# P-LED-0003-V1A_EAGLE_Schematic.net
KiCad netlist of a schematic drawn in EAGLE
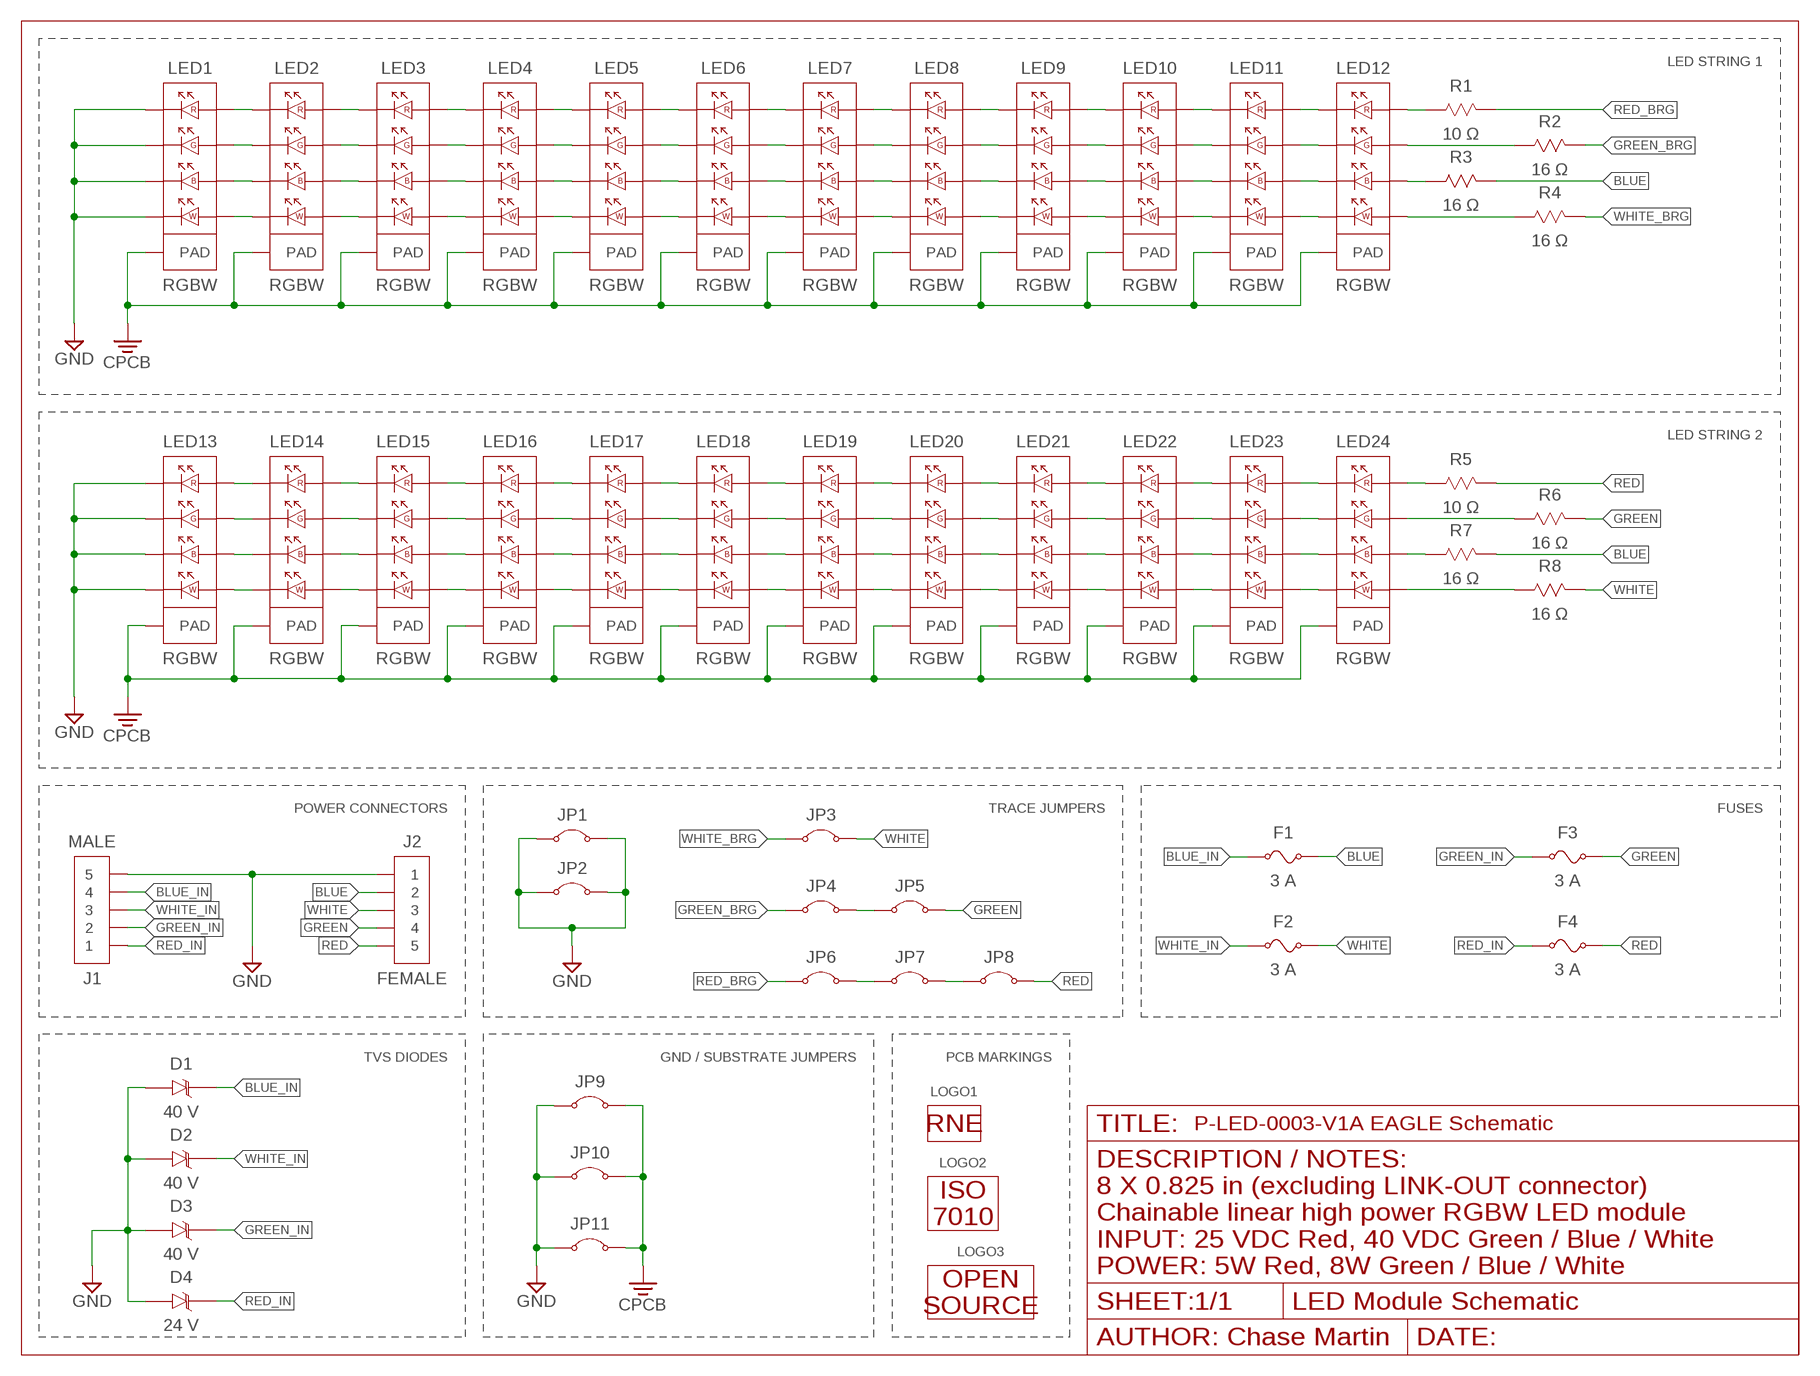
[diagram p0: schematic, sheet 1]

(export (version "E")
  (design (tool "Eeschema 10.0.6"))
  (components
    (comp (ref "D1")
      (value "40 V")
      (footprint "eagle-import:0603_POLARIZED")
      (libsource (lib "eagle-import") (part "UNIDIRECTIONAL_TVS_DIODESMD_0603"))
    )
    (comp (ref "D2")
      (value "40 V")
      (footprint "eagle-import:0603_POLARIZED")
      (libsource (lib "eagle-import") (part "UNIDIRECTIONAL_TVS_DIODESMD_0603"))
    )
    (comp (ref "D3")
      (value "40 V")
      (footprint "eagle-import:0603_POLARIZED")
      (libsource (lib "eagle-import") (part "UNIDIRECTIONAL_TVS_DIODESMD_0603"))
    )
    (comp (ref "D4")
      (value "24 V")
      (footprint "eagle-import:0603_POLARIZED")
      (libsource (lib "eagle-import") (part "UNIDIRECTIONAL_TVS_DIODESMD_0603"))
    )
    (comp (ref "F1")
      (value "3 A")
      (footprint "eagle-import:1206")
      (libsource (lib "eagle-import") (part "FUSESMD_1206"))
    )
    (comp (ref "F2")
      (value "3 A")
      (footprint "eagle-import:1206")
      (libsource (lib "eagle-import") (part "FUSESMD_1206"))
    )
    (comp (ref "F3")
      (value "3 A")
      (footprint "eagle-import:1206")
      (libsource (lib "eagle-import") (part "FUSESMD_1206"))
    )
    (comp (ref "F4")
      (value "3 A")
      (footprint "eagle-import:1206")
      (libsource (lib "eagle-import") (part "FUSESMD_1206"))
    )
    (comp (ref "J1")
      (value "MALE")
      (footprint "eagle-import:5-PIN_1-ROW_MALE_SMD_HORIZONTAL")
      (libsource (lib "eagle-import") (part "5-PIN_1-ROWMALE_SMD_HORIZONTAL"))
    )
    (comp (ref "J2")
      (value "FEMALE")
      (footprint "eagle-import:5-PIN_1-ROW_FEMALE_SMD_HORIZONTAL")
      (libsource (lib "eagle-import") (part "5-PIN_1-ROWFEMALE_SMD_HORIZONTAL"))
    )
    (comp (ref "JP1")
      (value "JUMPERSMD_1206")
      (footprint "eagle-import:1206")
      (libsource (lib "eagle-import") (part "JUMPERSMD_1206"))
    )
    (comp (ref "JP2")
      (value "JUMPERSMD_1206")
      (footprint "eagle-import:1206")
      (libsource (lib "eagle-import") (part "JUMPERSMD_1206"))
    )
    (comp (ref "JP3")
      (value "JUMPERSMD_1206")
      (footprint "eagle-import:1206")
      (libsource (lib "eagle-import") (part "JUMPERSMD_1206"))
    )
    (comp (ref "JP4")
      (value "JUMPERSMD_1206")
      (footprint "eagle-import:1206")
      (libsource (lib "eagle-import") (part "JUMPERSMD_1206"))
    )
    (comp (ref "JP5")
      (value "JUMPERSMD_1206")
      (footprint "eagle-import:1206")
      (libsource (lib "eagle-import") (part "JUMPERSMD_1206"))
    )
    (comp (ref "JP6")
      (value "JUMPERSMD_1206")
      (footprint "eagle-import:1206")
      (libsource (lib "eagle-import") (part "JUMPERSMD_1206"))
    )
    (comp (ref "JP7")
      (value "JUMPERSMD_1206")
      (footprint "eagle-import:1206")
      (libsource (lib "eagle-import") (part "JUMPERSMD_1206"))
    )
    (comp (ref "JP8")
      (value "JUMPERSMD_1206")
      (footprint "eagle-import:1206")
      (libsource (lib "eagle-import") (part "JUMPERSMD_1206"))
    )
    (comp (ref "JP9")
      (value "DCH_JUMPERSMD_0603")
      (footprint "eagle-import:0603")
      (libsource (lib "eagle-import") (part "DCH_JUMPERSMD_0603"))
    )
    (comp (ref "JP10")
      (value "DCH_JUMPERSMD_0603")
      (footprint "eagle-import:0603")
      (libsource (lib "eagle-import") (part "DCH_JUMPERSMD_0603"))
    )
    (comp (ref "JP11")
      (value "DCH_JUMPERSMD_0603")
      (footprint "eagle-import:0603")
      (libsource (lib "eagle-import") (part "DCH_JUMPERSMD_0603"))
    )
    (comp (ref "LED1")
      (value "RGBW")
      (footprint "eagle-import:IN-P55QSTGRGBW")
      (libsource (lib "eagle-import") (part "IN-P55QSTGRGBWPLCC8"))
    )
    (comp (ref "LED2")
      (value "RGBW")
      (footprint "eagle-import:IN-P55QSTGRGBW")
      (libsource (lib "eagle-import") (part "IN-P55QSTGRGBWPLCC8"))
    )
    (comp (ref "LED3")
      (value "RGBW")
      (footprint "eagle-import:IN-P55QSTGRGBW")
      (libsource (lib "eagle-import") (part "IN-P55QSTGRGBWPLCC8"))
    )
    (comp (ref "LED4")
      (value "RGBW")
      (footprint "eagle-import:IN-P55QSTGRGBW")
      (libsource (lib "eagle-import") (part "IN-P55QSTGRGBWPLCC8"))
    )
    (comp (ref "LED5")
      (value "RGBW")
      (footprint "eagle-import:IN-P55QSTGRGBW")
      (libsource (lib "eagle-import") (part "IN-P55QSTGRGBWPLCC8"))
    )
    (comp (ref "LED6")
      (value "RGBW")
      (footprint "eagle-import:IN-P55QSTGRGBW")
      (libsource (lib "eagle-import") (part "IN-P55QSTGRGBWPLCC8"))
    )
    (comp (ref "LED7")
      (value "RGBW")
      (footprint "eagle-import:IN-P55QSTGRGBW")
      (libsource (lib "eagle-import") (part "IN-P55QSTGRGBWPLCC8"))
    )
    (comp (ref "LED8")
      (value "RGBW")
      (footprint "eagle-import:IN-P55QSTGRGBW")
      (libsource (lib "eagle-import") (part "IN-P55QSTGRGBWPLCC8"))
    )
    (comp (ref "LED9")
      (value "RGBW")
      (footprint "eagle-import:IN-P55QSTGRGBW")
      (libsource (lib "eagle-import") (part "IN-P55QSTGRGBWPLCC8"))
    )
    (comp (ref "LED10")
      (value "RGBW")
      (footprint "eagle-import:IN-P55QSTGRGBW")
      (libsource (lib "eagle-import") (part "IN-P55QSTGRGBWPLCC8"))
    )
    (comp (ref "LED11")
      (value "RGBW")
      (footprint "eagle-import:IN-P55QSTGRGBW")
      (libsource (lib "eagle-import") (part "IN-P55QSTGRGBWPLCC8"))
    )
    (comp (ref "LED12")
      (value "RGBW")
      (footprint "eagle-import:IN-P55QSTGRGBW")
      (libsource (lib "eagle-import") (part "IN-P55QSTGRGBWPLCC8"))
    )
    (comp (ref "LED13")
      (value "RGBW")
      (footprint "eagle-import:IN-P55QSTGRGBW")
      (libsource (lib "eagle-import") (part "IN-P55QSTGRGBWPLCC8"))
    )
    (comp (ref "LED14")
      (value "RGBW")
      (footprint "eagle-import:IN-P55QSTGRGBW")
      (libsource (lib "eagle-import") (part "IN-P55QSTGRGBWPLCC8"))
    )
    (comp (ref "LED15")
      (value "RGBW")
      (footprint "eagle-import:IN-P55QSTGRGBW")
      (libsource (lib "eagle-import") (part "IN-P55QSTGRGBWPLCC8"))
    )
    (comp (ref "LED16")
      (value "RGBW")
      (footprint "eagle-import:IN-P55QSTGRGBW")
      (libsource (lib "eagle-import") (part "IN-P55QSTGRGBWPLCC8"))
    )
    (comp (ref "LED17")
      (value "RGBW")
      (footprint "eagle-import:IN-P55QSTGRGBW")
      (libsource (lib "eagle-import") (part "IN-P55QSTGRGBWPLCC8"))
    )
    (comp (ref "LED18")
      (value "RGBW")
      (footprint "eagle-import:IN-P55QSTGRGBW")
      (libsource (lib "eagle-import") (part "IN-P55QSTGRGBWPLCC8"))
    )
    (comp (ref "LED19")
      (value "RGBW")
      (footprint "eagle-import:IN-P55QSTGRGBW")
      (libsource (lib "eagle-import") (part "IN-P55QSTGRGBWPLCC8"))
    )
    (comp (ref "LED20")
      (value "RGBW")
      (footprint "eagle-import:IN-P55QSTGRGBW")
      (libsource (lib "eagle-import") (part "IN-P55QSTGRGBWPLCC8"))
    )
    (comp (ref "LED21")
      (value "RGBW")
      (footprint "eagle-import:IN-P55QSTGRGBW")
      (libsource (lib "eagle-import") (part "IN-P55QSTGRGBWPLCC8"))
    )
    (comp (ref "LED22")
      (value "RGBW")
      (footprint "eagle-import:IN-P55QSTGRGBW")
      (libsource (lib "eagle-import") (part "IN-P55QSTGRGBWPLCC8"))
    )
    (comp (ref "LED23")
      (value "RGBW")
      (footprint "eagle-import:IN-P55QSTGRGBW")
      (libsource (lib "eagle-import") (part "IN-P55QSTGRGBWPLCC8"))
    )
    (comp (ref "LED24")
      (value "RGBW")
      (footprint "eagle-import:IN-P55QSTGRGBW")
      (libsource (lib "eagle-import") (part "IN-P55QSTGRGBWPLCC8"))
    )
    (comp (ref "LOGO1")
      (value "PROFILE_LOGO_RNE0.375\"")
      (footprint "eagle-import:RNE_PROFILE-LOGO_375")
      (libsource (lib "eagle-import") (part "PROFILE_LOGO_RNE0.375{dblquote}"))
    )
    (comp (ref "LOGO2")
      (value "HOT_SURFACE_ISO0.375\"_LABEL")
      (footprint "eagle-import:ISO_HOT-SURFACE_375_LABEL")
      (libsource (lib "eagle-import") (part "HOT_SURFACE_ISO0.375{dblquote}_LABEL"))
    )
    (comp (ref "LOGO3")
      (value "OPEN_SOURCE_OSHWA0.375\"_LABEL")
      (footprint "eagle-import:OSHWA_OPEN-SOURCE_375_LABEL")
      (libsource (lib "eagle-import") (part "OPEN_SOURCE_OSHWA0.375{dblquote}_LABEL"))
    )
    (comp (ref "R1")
      (value "10 Ω")
      (footprint "eagle-import:0603")
      (libsource (lib "eagle-import") (part "RESISTORSMD_0603"))
    )
    (comp (ref "R2")
      (value "16 Ω")
      (footprint "eagle-import:0603")
      (libsource (lib "eagle-import") (part "RESISTORSMD_0603"))
    )
    (comp (ref "R3")
      (value "16 Ω")
      (footprint "eagle-import:0603")
      (libsource (lib "eagle-import") (part "RESISTORSMD_0603"))
    )
    (comp (ref "R4")
      (value "16 Ω")
      (footprint "eagle-import:0603")
      (libsource (lib "eagle-import") (part "RESISTORSMD_0603"))
    )
    (comp (ref "R5")
      (value "10 Ω")
      (footprint "eagle-import:0603")
      (libsource (lib "eagle-import") (part "RESISTORSMD_0603"))
    )
    (comp (ref "R6")
      (value "16 Ω")
      (footprint "eagle-import:0603")
      (libsource (lib "eagle-import") (part "RESISTORSMD_0603"))
    )
    (comp (ref "R7")
      (value "16 Ω")
      (footprint "eagle-import:0603")
      (libsource (lib "eagle-import") (part "RESISTORSMD_0603"))
    )
    (comp (ref "R8")
      (value "16 Ω")
      (footprint "eagle-import:0603")
      (libsource (lib "eagle-import") (part "RESISTORSMD_0603"))
    )
  )
  (nets
    (net (code "1") (name "BLUE") (class "Default")
      (node (ref "F1") (pin "2") (pinfunction "2_2") (pintype "passive"))
      (node (ref "J2") (pin "2") (pinfunction "2_2") (pintype "passive"))
      (node (ref "R3") (pin "2") (pinfunction "2_2") (pintype "passive"))
      (node (ref "R7") (pin "2") (pinfunction "2_2") (pintype "passive"))
    )
    (net (code "2") (name "BLUE_IN") (class "Default")
      (node (ref "D1") (pin "K") (pinfunction "K_K") (pintype "passive"))
      (node (ref "F1") (pin "1") (pinfunction "1_1") (pintype "passive"))
      (node (ref "J1") (pin "4") (pinfunction "4_4") (pintype "passive"))
    )
    (net (code "3") (name "CPCB") (class "Default")
      (node (ref "JP10") (pin "2") (pinfunction "2_2") (pintype "passive"))
      (node (ref "JP11") (pin "2") (pinfunction "2_2") (pintype "passive"))
      (node (ref "JP9") (pin "2") (pinfunction "2_2") (pintype "passive"))
      (node (ref "LED1") (pin "PAD") (pinfunction "PAD_PAD") (pintype "passive"))
      (node (ref "LED10") (pin "PAD") (pinfunction "PAD_PAD") (pintype "passive"))
      (node (ref "LED11") (pin "PAD") (pinfunction "PAD_PAD") (pintype "passive"))
      (node (ref "LED12") (pin "PAD") (pinfunction "PAD_PAD") (pintype "passive"))
      (node (ref "LED13") (pin "PAD") (pinfunction "PAD_PAD") (pintype "passive"))
      (node (ref "LED14") (pin "PAD") (pinfunction "PAD_PAD") (pintype "passive"))
      (node (ref "LED15") (pin "PAD") (pinfunction "PAD_PAD") (pintype "passive"))
      (node (ref "LED16") (pin "PAD") (pinfunction "PAD_PAD") (pintype "passive"))
      (node (ref "LED17") (pin "PAD") (pinfunction "PAD_PAD") (pintype "passive"))
      (node (ref "LED18") (pin "PAD") (pinfunction "PAD_PAD") (pintype "passive"))
      (node (ref "LED19") (pin "PAD") (pinfunction "PAD_PAD") (pintype "passive"))
      (node (ref "LED2") (pin "PAD") (pinfunction "PAD_PAD") (pintype "passive"))
      (node (ref "LED20") (pin "PAD") (pinfunction "PAD_PAD") (pintype "passive"))
      (node (ref "LED21") (pin "PAD") (pinfunction "PAD_PAD") (pintype "passive"))
      (node (ref "LED22") (pin "PAD") (pinfunction "PAD_PAD") (pintype "passive"))
      (node (ref "LED23") (pin "PAD") (pinfunction "PAD_PAD") (pintype "passive"))
      (node (ref "LED24") (pin "PAD") (pinfunction "PAD_PAD") (pintype "passive"))
      (node (ref "LED3") (pin "PAD") (pinfunction "PAD_PAD") (pintype "passive"))
      (node (ref "LED4") (pin "PAD") (pinfunction "PAD_PAD") (pintype "passive"))
      (node (ref "LED5") (pin "PAD") (pinfunction "PAD_PAD") (pintype "passive"))
      (node (ref "LED6") (pin "PAD") (pinfunction "PAD_PAD") (pintype "passive"))
      (node (ref "LED7") (pin "PAD") (pinfunction "PAD_PAD") (pintype "passive"))
      (node (ref "LED8") (pin "PAD") (pinfunction "PAD_PAD") (pintype "passive"))
      (node (ref "LED9") (pin "PAD") (pinfunction "PAD_PAD") (pintype "passive"))
    )
    (net (code "4") (name "GND") (class "Default")
      (node (ref "D1") (pin "A") (pinfunction "A_A") (pintype "passive"))
      (node (ref "D2") (pin "A") (pinfunction "A_A") (pintype "passive"))
      (node (ref "D3") (pin "A") (pinfunction "A_A") (pintype "passive"))
      (node (ref "D4") (pin "A") (pinfunction "A_A") (pintype "passive"))
      (node (ref "J1") (pin "5") (pinfunction "5_5") (pintype "passive"))
      (node (ref "J2") (pin "1") (pinfunction "1_1") (pintype "passive"))
      (node (ref "JP1") (pin "1") (pinfunction "1_1") (pintype "passive"))
      (node (ref "JP1") (pin "2") (pinfunction "2_2") (pintype "passive"))
      (node (ref "JP10") (pin "1") (pinfunction "1_1") (pintype "passive"))
      (node (ref "JP11") (pin "1") (pinfunction "1_1") (pintype "passive"))
      (node (ref "JP2") (pin "1") (pinfunction "1_1") (pintype "passive"))
      (node (ref "JP2") (pin "2") (pinfunction "2_2") (pintype "passive"))
      (node (ref "JP9") (pin "1") (pinfunction "1_1") (pintype "passive"))
      (node (ref "LED1") (pin "BLUE_N") (pinfunction "BLUE_N_BLUE_N") (pintype "output"))
      (node (ref "LED1") (pin "GREEN_N") (pinfunction "GREEN_N_GREEN_N") (pintype "output"))
      (node (ref "LED1") (pin "RED_N") (pinfunction "RED_N_RED_N") (pintype "output"))
      (node (ref "LED1") (pin "WHITE_N") (pinfunction "WHITE_N_WHITE_N") (pintype "output"))
      (node (ref "LED13") (pin "BLUE_N") (pinfunction "BLUE_N_BLUE_N") (pintype "output"))
      (node (ref "LED13") (pin "GREEN_N") (pinfunction "GREEN_N_GREEN_N") (pintype "output"))
      (node (ref "LED13") (pin "RED_N") (pinfunction "RED_N_RED_N") (pintype "output"))
      (node (ref "LED13") (pin "WHITE_N") (pinfunction "WHITE_N_WHITE_N") (pintype "output"))
    )
    (net (code "5") (name "GREEN") (class "Default")
      (node (ref "F3") (pin "2") (pinfunction "2_2") (pintype "passive"))
      (node (ref "J2") (pin "4") (pinfunction "4_4") (pintype "passive"))
      (node (ref "JP5") (pin "2") (pinfunction "2_2") (pintype "passive"))
      (node (ref "R6") (pin "2") (pinfunction "2_2") (pintype "passive"))
    )
    (net (code "6") (name "GREEN_BRG") (class "Default")
      (node (ref "JP4") (pin "1") (pinfunction "1_1") (pintype "passive"))
      (node (ref "R2") (pin "2") (pinfunction "2_2") (pintype "passive"))
    )
    (net (code "7") (name "GREEN_IN") (class "Default")
      (node (ref "D3") (pin "K") (pinfunction "K_K") (pintype "passive"))
      (node (ref "F3") (pin "1") (pinfunction "1_1") (pintype "passive"))
      (node (ref "J1") (pin "2") (pinfunction "2_2") (pintype "passive"))
    )
    (net (code "8") (name "Net-(JP4-Pad2)") (class "Default")
      (node (ref "JP4") (pin "2") (pinfunction "2_2") (pintype "passive"))
      (node (ref "JP5") (pin "1") (pinfunction "1_1") (pintype "passive"))
    )
    (net (code "9") (name "Net-(JP6-Pad2)") (class "Default")
      (node (ref "JP6") (pin "2") (pinfunction "2_2") (pintype "passive"))
      (node (ref "JP7") (pin "1") (pinfunction "1_1") (pintype "passive"))
    )
    (net (code "10") (name "Net-(JP7-Pad2)") (class "Default")
      (node (ref "JP7") (pin "2") (pinfunction "2_2") (pintype "passive"))
      (node (ref "JP8") (pin "1") (pinfunction "1_1") (pintype "passive"))
    )
    (net (code "11") (name "Net-(LED1-PadBLUE_P)") (class "Default")
      (node (ref "LED1") (pin "BLUE_P") (pinfunction "BLUE_P_BLUE_P") (pintype "input"))
      (node (ref "LED2") (pin "BLUE_N") (pinfunction "BLUE_N_BLUE_N") (pintype "output"))
    )
    (net (code "12") (name "Net-(LED1-PadGREEN_P)") (class "Default")
      (node (ref "LED1") (pin "GREEN_P") (pinfunction "GREEN_P_GREEN_P") (pintype "input"))
      (node (ref "LED2") (pin "GREEN_N") (pinfunction "GREEN_N_GREEN_N") (pintype "output"))
    )
    (net (code "13") (name "Net-(LED1-PadRED_P)") (class "Default")
      (node (ref "LED1") (pin "RED_P") (pinfunction "RED_P_RED_P") (pintype "input"))
      (node (ref "LED2") (pin "RED_N") (pinfunction "RED_N_RED_N") (pintype "output"))
    )
    (net (code "14") (name "Net-(LED1-PadWHITE_P)") (class "Default")
      (node (ref "LED1") (pin "WHITE_P") (pinfunction "WHITE_P_WHITE_P") (pintype "input"))
      (node (ref "LED2") (pin "WHITE_N") (pinfunction "WHITE_N_WHITE_N") (pintype "output"))
    )
    (net (code "15") (name "Net-(LED2-PadBLUE_P)") (class "Default")
      (node (ref "LED2") (pin "BLUE_P") (pinfunction "BLUE_P_BLUE_P") (pintype "input"))
      (node (ref "LED3") (pin "BLUE_N") (pinfunction "BLUE_N_BLUE_N") (pintype "output"))
    )
    (net (code "16") (name "Net-(LED2-PadGREEN_P)") (class "Default")
      (node (ref "LED2") (pin "GREEN_P") (pinfunction "GREEN_P_GREEN_P") (pintype "input"))
      (node (ref "LED3") (pin "GREEN_N") (pinfunction "GREEN_N_GREEN_N") (pintype "output"))
    )
    (net (code "17") (name "Net-(LED2-PadRED_P)") (class "Default")
      (node (ref "LED2") (pin "RED_P") (pinfunction "RED_P_RED_P") (pintype "input"))
      (node (ref "LED3") (pin "RED_N") (pinfunction "RED_N_RED_N") (pintype "output"))
    )
    (net (code "18") (name "Net-(LED2-PadWHITE_P)") (class "Default")
      (node (ref "LED2") (pin "WHITE_P") (pinfunction "WHITE_P_WHITE_P") (pintype "input"))
      (node (ref "LED3") (pin "WHITE_N") (pinfunction "WHITE_N_WHITE_N") (pintype "output"))
    )
    (net (code "19") (name "Net-(LED3-PadBLUE_P)") (class "Default")
      (node (ref "LED3") (pin "BLUE_P") (pinfunction "BLUE_P_BLUE_P") (pintype "input"))
      (node (ref "LED4") (pin "BLUE_N") (pinfunction "BLUE_N_BLUE_N") (pintype "output"))
    )
    (net (code "20") (name "Net-(LED3-PadGREEN_P)") (class "Default")
      (node (ref "LED3") (pin "GREEN_P") (pinfunction "GREEN_P_GREEN_P") (pintype "input"))
      (node (ref "LED4") (pin "GREEN_N") (pinfunction "GREEN_N_GREEN_N") (pintype "output"))
    )
    (net (code "21") (name "Net-(LED3-PadRED_P)") (class "Default")
      (node (ref "LED3") (pin "RED_P") (pinfunction "RED_P_RED_P") (pintype "input"))
      (node (ref "LED4") (pin "RED_N") (pinfunction "RED_N_RED_N") (pintype "output"))
    )
    (net (code "22") (name "Net-(LED3-PadWHITE_P)") (class "Default")
      (node (ref "LED3") (pin "WHITE_P") (pinfunction "WHITE_P_WHITE_P") (pintype "input"))
      (node (ref "LED4") (pin "WHITE_N") (pinfunction "WHITE_N_WHITE_N") (pintype "output"))
    )
    (net (code "23") (name "Net-(LED4-PadBLUE_P)") (class "Default")
      (node (ref "LED4") (pin "BLUE_P") (pinfunction "BLUE_P_BLUE_P") (pintype "input"))
      (node (ref "LED5") (pin "BLUE_N") (pinfunction "BLUE_N_BLUE_N") (pintype "output"))
    )
    (net (code "24") (name "Net-(LED4-PadGREEN_P)") (class "Default")
      (node (ref "LED4") (pin "GREEN_P") (pinfunction "GREEN_P_GREEN_P") (pintype "input"))
      (node (ref "LED5") (pin "GREEN_N") (pinfunction "GREEN_N_GREEN_N") (pintype "output"))
    )
    (net (code "25") (name "Net-(LED4-PadRED_P)") (class "Default")
      (node (ref "LED4") (pin "RED_P") (pinfunction "RED_P_RED_P") (pintype "input"))
      (node (ref "LED5") (pin "RED_N") (pinfunction "RED_N_RED_N") (pintype "output"))
    )
    (net (code "26") (name "Net-(LED4-PadWHITE_P)") (class "Default")
      (node (ref "LED4") (pin "WHITE_P") (pinfunction "WHITE_P_WHITE_P") (pintype "input"))
      (node (ref "LED5") (pin "WHITE_N") (pinfunction "WHITE_N_WHITE_N") (pintype "output"))
    )
    (net (code "27") (name "Net-(LED5-PadBLUE_P)") (class "Default")
      (node (ref "LED5") (pin "BLUE_P") (pinfunction "BLUE_P_BLUE_P") (pintype "input"))
      (node (ref "LED6") (pin "BLUE_N") (pinfunction "BLUE_N_BLUE_N") (pintype "output"))
    )
    (net (code "28") (name "Net-(LED5-PadGREEN_P)") (class "Default")
      (node (ref "LED5") (pin "GREEN_P") (pinfunction "GREEN_P_GREEN_P") (pintype "input"))
      (node (ref "LED6") (pin "GREEN_N") (pinfunction "GREEN_N_GREEN_N") (pintype "output"))
    )
    (net (code "29") (name "Net-(LED5-PadRED_P)") (class "Default")
      (node (ref "LED5") (pin "RED_P") (pinfunction "RED_P_RED_P") (pintype "input"))
      (node (ref "LED6") (pin "RED_N") (pinfunction "RED_N_RED_N") (pintype "output"))
    )
    (net (code "30") (name "Net-(LED5-PadWHITE_P)") (class "Default")
      (node (ref "LED5") (pin "WHITE_P") (pinfunction "WHITE_P_WHITE_P") (pintype "input"))
      (node (ref "LED6") (pin "WHITE_N") (pinfunction "WHITE_N_WHITE_N") (pintype "output"))
    )
    (net (code "31") (name "Net-(LED6-PadBLUE_P)") (class "Default")
      (node (ref "LED6") (pin "BLUE_P") (pinfunction "BLUE_P_BLUE_P") (pintype "input"))
      (node (ref "LED7") (pin "BLUE_N") (pinfunction "BLUE_N_BLUE_N") (pintype "output"))
    )
    (net (code "32") (name "Net-(LED6-PadGREEN_P)") (class "Default")
      (node (ref "LED6") (pin "GREEN_P") (pinfunction "GREEN_P_GREEN_P") (pintype "input"))
      (node (ref "LED7") (pin "GREEN_N") (pinfunction "GREEN_N_GREEN_N") (pintype "output"))
    )
    (net (code "33") (name "Net-(LED6-PadRED_P)") (class "Default")
      (node (ref "LED6") (pin "RED_P") (pinfunction "RED_P_RED_P") (pintype "input"))
      (node (ref "LED7") (pin "RED_N") (pinfunction "RED_N_RED_N") (pintype "output"))
    )
    (net (code "34") (name "Net-(LED6-PadWHITE_P)") (class "Default")
      (node (ref "LED6") (pin "WHITE_P") (pinfunction "WHITE_P_WHITE_P") (pintype "input"))
      (node (ref "LED7") (pin "WHITE_N") (pinfunction "WHITE_N_WHITE_N") (pintype "output"))
    )
    (net (code "35") (name "Net-(LED7-PadBLUE_P)") (class "Default")
      (node (ref "LED7") (pin "BLUE_P") (pinfunction "BLUE_P_BLUE_P") (pintype "input"))
      (node (ref "LED8") (pin "BLUE_N") (pinfunction "BLUE_N_BLUE_N") (pintype "output"))
    )
    (net (code "36") (name "Net-(LED7-PadGREEN_P)") (class "Default")
      (node (ref "LED7") (pin "GREEN_P") (pinfunction "GREEN_P_GREEN_P") (pintype "input"))
      (node (ref "LED8") (pin "GREEN_N") (pinfunction "GREEN_N_GREEN_N") (pintype "output"))
    )
    (net (code "37") (name "Net-(LED7-PadRED_P)") (class "Default")
      (node (ref "LED7") (pin "RED_P") (pinfunction "RED_P_RED_P") (pintype "input"))
      (node (ref "LED8") (pin "RED_N") (pinfunction "RED_N_RED_N") (pintype "output"))
    )
    (net (code "38") (name "Net-(LED7-PadWHITE_P)") (class "Default")
      (node (ref "LED7") (pin "WHITE_P") (pinfunction "WHITE_P_WHITE_P") (pintype "input"))
      (node (ref "LED8") (pin "WHITE_N") (pinfunction "WHITE_N_WHITE_N") (pintype "output"))
    )
    (net (code "39") (name "Net-(LED8-PadBLUE_P)") (class "Default")
      (node (ref "LED8") (pin "BLUE_P") (pinfunction "BLUE_P_BLUE_P") (pintype "input"))
      (node (ref "LED9") (pin "BLUE_N") (pinfunction "BLUE_N_BLUE_N") (pintype "output"))
    )
    (net (code "40") (name "Net-(LED8-PadGREEN_P)") (class "Default")
      (node (ref "LED8") (pin "GREEN_P") (pinfunction "GREEN_P_GREEN_P") (pintype "input"))
      (node (ref "LED9") (pin "GREEN_N") (pinfunction "GREEN_N_GREEN_N") (pintype "output"))
    )
    (net (code "41") (name "Net-(LED8-PadRED_P)") (class "Default")
      (node (ref "LED8") (pin "RED_P") (pinfunction "RED_P_RED_P") (pintype "input"))
      (node (ref "LED9") (pin "RED_N") (pinfunction "RED_N_RED_N") (pintype "output"))
    )
    (net (code "42") (name "Net-(LED8-PadWHITE_P)") (class "Default")
      (node (ref "LED8") (pin "WHITE_P") (pinfunction "WHITE_P_WHITE_P") (pintype "input"))
      (node (ref "LED9") (pin "WHITE_N") (pinfunction "WHITE_N_WHITE_N") (pintype "output"))
    )
    (net (code "43") (name "Net-(LED10-PadBLUE_N)") (class "Default")
      (node (ref "LED10") (pin "BLUE_N") (pinfunction "BLUE_N_BLUE_N") (pintype "output"))
      (node (ref "LED9") (pin "BLUE_P") (pinfunction "BLUE_P_BLUE_P") (pintype "input"))
    )
    (net (code "44") (name "Net-(LED10-PadBLUE_P)") (class "Default")
      (node (ref "LED10") (pin "BLUE_P") (pinfunction "BLUE_P_BLUE_P") (pintype "input"))
      (node (ref "LED11") (pin "BLUE_N") (pinfunction "BLUE_N_BLUE_N") (pintype "output"))
    )
    (net (code "45") (name "Net-(LED10-PadGREEN_N)") (class "Default")
      (node (ref "LED10") (pin "GREEN_N") (pinfunction "GREEN_N_GREEN_N") (pintype "output"))
      (node (ref "LED9") (pin "GREEN_P") (pinfunction "GREEN_P_GREEN_P") (pintype "input"))
    )
    (net (code "46") (name "Net-(LED10-PadGREEN_P)") (class "Default")
      (node (ref "LED10") (pin "GREEN_P") (pinfunction "GREEN_P_GREEN_P") (pintype "input"))
      (node (ref "LED11") (pin "GREEN_N") (pinfunction "GREEN_N_GREEN_N") (pintype "output"))
    )
    (net (code "47") (name "Net-(LED10-PadRED_N)") (class "Default")
      (node (ref "LED10") (pin "RED_N") (pinfunction "RED_N_RED_N") (pintype "output"))
      (node (ref "LED9") (pin "RED_P") (pinfunction "RED_P_RED_P") (pintype "input"))
    )
    (net (code "48") (name "Net-(LED10-PadRED_P)") (class "Default")
      (node (ref "LED10") (pin "RED_P") (pinfunction "RED_P_RED_P") (pintype "input"))
      (node (ref "LED11") (pin "RED_N") (pinfunction "RED_N_RED_N") (pintype "output"))
    )
    (net (code "49") (name "Net-(LED10-PadWHITE_N)") (class "Default")
      (node (ref "LED10") (pin "WHITE_N") (pinfunction "WHITE_N_WHITE_N") (pintype "output"))
      (node (ref "LED9") (pin "WHITE_P") (pinfunction "WHITE_P_WHITE_P") (pintype "input"))
    )
    (net (code "50") (name "Net-(LED10-PadWHITE_P)") (class "Default")
      (node (ref "LED10") (pin "WHITE_P") (pinfunction "WHITE_P_WHITE_P") (pintype "input"))
      (node (ref "LED11") (pin "WHITE_N") (pinfunction "WHITE_N_WHITE_N") (pintype "output"))
    )
    (net (code "51") (name "Net-(LED11-PadBLUE_P)") (class "Default")
      (node (ref "LED11") (pin "BLUE_P") (pinfunction "BLUE_P_BLUE_P") (pintype "input"))
      (node (ref "LED12") (pin "BLUE_N") (pinfunction "BLUE_N_BLUE_N") (pintype "output"))
    )
    (net (code "52") (name "Net-(LED11-PadGREEN_P)") (class "Default")
      (node (ref "LED11") (pin "GREEN_P") (pinfunction "GREEN_P_GREEN_P") (pintype "input"))
      (node (ref "LED12") (pin "GREEN_N") (pinfunction "GREEN_N_GREEN_N") (pintype "output"))
    )
    (net (code "53") (name "Net-(LED11-PadRED_P)") (class "Default")
      (node (ref "LED11") (pin "RED_P") (pinfunction "RED_P_RED_P") (pintype "input"))
      (node (ref "LED12") (pin "RED_N") (pinfunction "RED_N_RED_N") (pintype "output"))
    )
    (net (code "54") (name "Net-(LED11-PadWHITE_P)") (class "Default")
      (node (ref "LED11") (pin "WHITE_P") (pinfunction "WHITE_P_WHITE_P") (pintype "input"))
      (node (ref "LED12") (pin "WHITE_N") (pinfunction "WHITE_N_WHITE_N") (pintype "output"))
    )
    (net (code "55") (name "Net-(LED12-PadBLUE_P)") (class "Default")
      (node (ref "LED12") (pin "BLUE_P") (pinfunction "BLUE_P_BLUE_P") (pintype "input"))
      (node (ref "R3") (pin "1") (pinfunction "1_1") (pintype "passive"))
    )
    (net (code "56") (name "Net-(LED12-PadGREEN_P)") (class "Default")
      (node (ref "LED12") (pin "GREEN_P") (pinfunction "GREEN_P_GREEN_P") (pintype "input"))
      (node (ref "R2") (pin "1") (pinfunction "1_1") (pintype "passive"))
    )
    (net (code "57") (name "Net-(LED12-PadRED_P)") (class "Default")
      (node (ref "LED12") (pin "RED_P") (pinfunction "RED_P_RED_P") (pintype "input"))
      (node (ref "R1") (pin "1") (pinfunction "1_1") (pintype "passive"))
    )
    (net (code "58") (name "Net-(LED12-PadWHITE_P)") (class "Default")
      (node (ref "LED12") (pin "WHITE_P") (pinfunction "WHITE_P_WHITE_P") (pintype "input"))
      (node (ref "R4") (pin "1") (pinfunction "1_1") (pintype "passive"))
    )
    (net (code "59") (name "Net-(LED13-PadBLUE_P)") (class "Default")
      (node (ref "LED13") (pin "BLUE_P") (pinfunction "BLUE_P_BLUE_P") (pintype "input"))
      (node (ref "LED14") (pin "BLUE_N") (pinfunction "BLUE_N_BLUE_N") (pintype "output"))
    )
    (net (code "60") (name "Net-(LED13-PadGREEN_P)") (class "Default")
      (node (ref "LED13") (pin "GREEN_P") (pinfunction "GREEN_P_GREEN_P") (pintype "input"))
      (node (ref "LED14") (pin "GREEN_N") (pinfunction "GREEN_N_GREEN_N") (pintype "output"))
    )
    (net (code "61") (name "Net-(LED13-PadRED_P)") (class "Default")
      (node (ref "LED13") (pin "RED_P") (pinfunction "RED_P_RED_P") (pintype "input"))
      (node (ref "LED14") (pin "RED_N") (pinfunction "RED_N_RED_N") (pintype "output"))
    )
    (net (code "62") (name "Net-(LED13-PadWHITE_P)") (class "Default")
      (node (ref "LED13") (pin "WHITE_P") (pinfunction "WHITE_P_WHITE_P") (pintype "input"))
      (node (ref "LED14") (pin "WHITE_N") (pinfunction "WHITE_N_WHITE_N") (pintype "output"))
    )
    (net (code "63") (name "Net-(LED14-PadBLUE_P)") (class "Default")
      (node (ref "LED14") (pin "BLUE_P") (pinfunction "BLUE_P_BLUE_P") (pintype "input"))
      (node (ref "LED15") (pin "BLUE_N") (pinfunction "BLUE_N_BLUE_N") (pintype "output"))
    )
    (net (code "64") (name "Net-(LED14-PadGREEN_P)") (class "Default")
      (node (ref "LED14") (pin "GREEN_P") (pinfunction "GREEN_P_GREEN_P") (pintype "input"))
      (node (ref "LED15") (pin "GREEN_N") (pinfunction "GREEN_N_GREEN_N") (pintype "output"))
    )
    (net (code "65") (name "Net-(LED14-PadRED_P)") (class "Default")
      (node (ref "LED14") (pin "RED_P") (pinfunction "RED_P_RED_P") (pintype "input"))
      (node (ref "LED15") (pin "RED_N") (pinfunction "RED_N_RED_N") (pintype "output"))
    )
    (net (code "66") (name "Net-(LED14-PadWHITE_P)") (class "Default")
      (node (ref "LED14") (pin "WHITE_P") (pinfunction "WHITE_P_WHITE_P") (pintype "input"))
      (node (ref "LED15") (pin "WHITE_N") (pinfunction "WHITE_N_WHITE_N") (pintype "output"))
    )
    (net (code "67") (name "Net-(LED15-PadBLUE_P)") (class "Default")
      (node (ref "LED15") (pin "BLUE_P") (pinfunction "BLUE_P_BLUE_P") (pintype "input"))
      (node (ref "LED16") (pin "BLUE_N") (pinfunction "BLUE_N_BLUE_N") (pintype "output"))
    )
    (net (code "68") (name "Net-(LED15-PadGREEN_P)") (class "Default")
      (node (ref "LED15") (pin "GREEN_P") (pinfunction "GREEN_P_GREEN_P") (pintype "input"))
      (node (ref "LED16") (pin "GREEN_N") (pinfunction "GREEN_N_GREEN_N") (pintype "output"))
    )
    (net (code "69") (name "Net-(LED15-PadRED_P)") (class "Default")
      (node (ref "LED15") (pin "RED_P") (pinfunction "RED_P_RED_P") (pintype "input"))
      (node (ref "LED16") (pin "RED_N") (pinfunction "RED_N_RED_N") (pintype "output"))
    )
    (net (code "70") (name "Net-(LED15-PadWHITE_P)") (class "Default")
      (node (ref "LED15") (pin "WHITE_P") (pinfunction "WHITE_P_WHITE_P") (pintype "input"))
      (node (ref "LED16") (pin "WHITE_N") (pinfunction "WHITE_N_WHITE_N") (pintype "output"))
    )
    (net (code "71") (name "Net-(LED16-PadBLUE_P)") (class "Default")
      (node (ref "LED16") (pin "BLUE_P") (pinfunction "BLUE_P_BLUE_P") (pintype "input"))
      (node (ref "LED17") (pin "BLUE_N") (pinfunction "BLUE_N_BLUE_N") (pintype "output"))
    )
    (net (code "72") (name "Net-(LED16-PadGREEN_P)") (class "Default")
      (node (ref "LED16") (pin "GREEN_P") (pinfunction "GREEN_P_GREEN_P") (pintype "input"))
      (node (ref "LED17") (pin "GREEN_N") (pinfunction "GREEN_N_GREEN_N") (pintype "output"))
    )
    (net (code "73") (name "Net-(LED16-PadRED_P)") (class "Default")
      (node (ref "LED16") (pin "RED_P") (pinfunction "RED_P_RED_P") (pintype "input"))
      (node (ref "LED17") (pin "RED_N") (pinfunction "RED_N_RED_N") (pintype "output"))
    )
    (net (code "74") (name "Net-(LED16-PadWHITE_P)") (class "Default")
      (node (ref "LED16") (pin "WHITE_P") (pinfunction "WHITE_P_WHITE_P") (pintype "input"))
      (node (ref "LED17") (pin "WHITE_N") (pinfunction "WHITE_N_WHITE_N") (pintype "output"))
    )
    (net (code "75") (name "Net-(LED17-PadBLUE_P)") (class "Default")
      (node (ref "LED17") (pin "BLUE_P") (pinfunction "BLUE_P_BLUE_P") (pintype "input"))
      (node (ref "LED18") (pin "BLUE_N") (pinfunction "BLUE_N_BLUE_N") (pintype "output"))
    )
    (net (code "76") (name "Net-(LED17-PadGREEN_P)") (class "Default")
      (node (ref "LED17") (pin "GREEN_P") (pinfunction "GREEN_P_GREEN_P") (pintype "input"))
      (node (ref "LED18") (pin "GREEN_N") (pinfunction "GREEN_N_GREEN_N") (pintype "output"))
    )
    (net (code "77") (name "Net-(LED17-PadRED_P)") (class "Default")
      (node (ref "LED17") (pin "RED_P") (pinfunction "RED_P_RED_P") (pintype "input"))
      (node (ref "LED18") (pin "RED_N") (pinfunction "RED_N_RED_N") (pintype "output"))
    )
    (net (code "78") (name "Net-(LED17-PadWHITE_P)") (class "Default")
      (node (ref "LED17") (pin "WHITE_P") (pinfunction "WHITE_P_WHITE_P") (pintype "input"))
      (node (ref "LED18") (pin "WHITE_N") (pinfunction "WHITE_N_WHITE_N") (pintype "output"))
    )
    (net (code "79") (name "Net-(LED18-PadBLUE_P)") (class "Default")
      (node (ref "LED18") (pin "BLUE_P") (pinfunction "BLUE_P_BLUE_P") (pintype "input"))
      (node (ref "LED19") (pin "BLUE_N") (pinfunction "BLUE_N_BLUE_N") (pintype "output"))
    )
    (net (code "80") (name "Net-(LED18-PadGREEN_P)") (class "Default")
      (node (ref "LED18") (pin "GREEN_P") (pinfunction "GREEN_P_GREEN_P") (pintype "input"))
      (node (ref "LED19") (pin "GREEN_N") (pinfunction "GREEN_N_GREEN_N") (pintype "output"))
    )
    (net (code "81") (name "Net-(LED18-PadRED_P)") (class "Default")
      (node (ref "LED18") (pin "RED_P") (pinfunction "RED_P_RED_P") (pintype "input"))
      (node (ref "LED19") (pin "RED_N") (pinfunction "RED_N_RED_N") (pintype "output"))
    )
    (net (code "82") (name "Net-(LED18-PadWHITE_P)") (class "Default")
      (node (ref "LED18") (pin "WHITE_P") (pinfunction "WHITE_P_WHITE_P") (pintype "input"))
      (node (ref "LED19") (pin "WHITE_N") (pinfunction "WHITE_N_WHITE_N") (pintype "output"))
    )
    (net (code "83") (name "Net-(LED19-PadBLUE_P)") (class "Default")
      (node (ref "LED19") (pin "BLUE_P") (pinfunction "BLUE_P_BLUE_P") (pintype "input"))
      (node (ref "LED20") (pin "BLUE_N") (pinfunction "BLUE_N_BLUE_N") (pintype "output"))
    )
    (net (code "84") (name "Net-(LED19-PadGREEN_P)") (class "Default")
      (node (ref "LED19") (pin "GREEN_P") (pinfunction "GREEN_P_GREEN_P") (pintype "input"))
      (node (ref "LED20") (pin "GREEN_N") (pinfunction "GREEN_N_GREEN_N") (pintype "output"))
    )
    (net (code "85") (name "Net-(LED19-PadRED_P)") (class "Default")
      (node (ref "LED19") (pin "RED_P") (pinfunction "RED_P_RED_P") (pintype "input"))
      (node (ref "LED20") (pin "RED_N") (pinfunction "RED_N_RED_N") (pintype "output"))
    )
    (net (code "86") (name "Net-(LED19-PadWHITE_P)") (class "Default")
      (node (ref "LED19") (pin "WHITE_P") (pinfunction "WHITE_P_WHITE_P") (pintype "input"))
      (node (ref "LED20") (pin "WHITE_N") (pinfunction "WHITE_N_WHITE_N") (pintype "output"))
    )
    (net (code "87") (name "Net-(LED20-PadBLUE_P)") (class "Default")
      (node (ref "LED20") (pin "BLUE_P") (pinfunction "BLUE_P_BLUE_P") (pintype "input"))
      (node (ref "LED21") (pin "BLUE_N") (pinfunction "BLUE_N_BLUE_N") (pintype "output"))
    )
    (net (code "88") (name "Net-(LED20-PadGREEN_P)") (class "Default")
      (node (ref "LED20") (pin "GREEN_P") (pinfunction "GREEN_P_GREEN_P") (pintype "input"))
      (node (ref "LED21") (pin "GREEN_N") (pinfunction "GREEN_N_GREEN_N") (pintype "output"))
    )
    (net (code "89") (name "Net-(LED20-PadRED_P)") (class "Default")
      (node (ref "LED20") (pin "RED_P") (pinfunction "RED_P_RED_P") (pintype "input"))
      (node (ref "LED21") (pin "RED_N") (pinfunction "RED_N_RED_N") (pintype "output"))
    )
    (net (code "90") (name "Net-(LED20-PadWHITE_P)") (class "Default")
      (node (ref "LED20") (pin "WHITE_P") (pinfunction "WHITE_P_WHITE_P") (pintype "input"))
      (node (ref "LED21") (pin "WHITE_N") (pinfunction "WHITE_N_WHITE_N") (pintype "output"))
    )
    (net (code "91") (name "Net-(LED21-PadBLUE_P)") (class "Default")
      (node (ref "LED21") (pin "BLUE_P") (pinfunction "BLUE_P_BLUE_P") (pintype "input"))
      (node (ref "LED22") (pin "BLUE_N") (pinfunction "BLUE_N_BLUE_N") (pintype "output"))
    )
    (net (code "92") (name "Net-(LED21-PadGREEN_P)") (class "Default")
      (node (ref "LED21") (pin "GREEN_P") (pinfunction "GREEN_P_GREEN_P") (pintype "input"))
      (node (ref "LED22") (pin "GREEN_N") (pinfunction "GREEN_N_GREEN_N") (pintype "output"))
    )
    (net (code "93") (name "Net-(LED21-PadRED_P)") (class "Default")
      (node (ref "LED21") (pin "RED_P") (pinfunction "RED_P_RED_P") (pintype "input"))
      (node (ref "LED22") (pin "RED_N") (pinfunction "RED_N_RED_N") (pintype "output"))
    )
    (net (code "94") (name "Net-(LED21-PadWHITE_P)") (class "Default")
      (node (ref "LED21") (pin "WHITE_P") (pinfunction "WHITE_P_WHITE_P") (pintype "input"))
      (node (ref "LED22") (pin "WHITE_N") (pinfunction "WHITE_N_WHITE_N") (pintype "output"))
    )
    (net (code "95") (name "Net-(LED22-PadBLUE_P)") (class "Default")
      (node (ref "LED22") (pin "BLUE_P") (pinfunction "BLUE_P_BLUE_P") (pintype "input"))
      (node (ref "LED23") (pin "BLUE_N") (pinfunction "BLUE_N_BLUE_N") (pintype "output"))
    )
    (net (code "96") (name "Net-(LED22-PadGREEN_P)") (class "Default")
      (node (ref "LED22") (pin "GREEN_P") (pinfunction "GREEN_P_GREEN_P") (pintype "input"))
      (node (ref "LED23") (pin "GREEN_N") (pinfunction "GREEN_N_GREEN_N") (pintype "output"))
    )
    (net (code "97") (name "Net-(LED22-PadRED_P)") (class "Default")
      (node (ref "LED22") (pin "RED_P") (pinfunction "RED_P_RED_P") (pintype "input"))
      (node (ref "LED23") (pin "RED_N") (pinfunction "RED_N_RED_N") (pintype "output"))
    )
    (net (code "98") (name "Net-(LED22-PadWHITE_P)") (class "Default")
      (node (ref "LED22") (pin "WHITE_P") (pinfunction "WHITE_P_WHITE_P") (pintype "input"))
      (node (ref "LED23") (pin "WHITE_N") (pinfunction "WHITE_N_WHITE_N") (pintype "output"))
    )
    (net (code "99") (name "Net-(LED23-PadBLUE_P)") (class "Default")
      (node (ref "LED23") (pin "BLUE_P") (pinfunction "BLUE_P_BLUE_P") (pintype "input"))
      (node (ref "LED24") (pin "BLUE_N") (pinfunction "BLUE_N_BLUE_N") (pintype "output"))
    )
    (net (code "100") (name "Net-(LED23-PadGREEN_P)") (class "Default")
      (node (ref "LED23") (pin "GREEN_P") (pinfunction "GREEN_P_GREEN_P") (pintype "input"))
      (node (ref "LED24") (pin "GREEN_N") (pinfunction "GREEN_N_GREEN_N") (pintype "output"))
    )
    (net (code "101") (name "Net-(LED23-PadRED_P)") (class "Default")
      (node (ref "LED23") (pin "RED_P") (pinfunction "RED_P_RED_P") (pintype "input"))
      (node (ref "LED24") (pin "RED_N") (pinfunction "RED_N_RED_N") (pintype "output"))
    )
    (net (code "102") (name "Net-(LED23-PadWHITE_P)") (class "Default")
      (node (ref "LED23") (pin "WHITE_P") (pinfunction "WHITE_P_WHITE_P") (pintype "input"))
      (node (ref "LED24") (pin "WHITE_N") (pinfunction "WHITE_N_WHITE_N") (pintype "output"))
    )
    (net (code "103") (name "Net-(LED24-PadBLUE_P)") (class "Default")
      (node (ref "LED24") (pin "BLUE_P") (pinfunction "BLUE_P_BLUE_P") (pintype "input"))
      (node (ref "R7") (pin "1") (pinfunction "1_1") (pintype "passive"))
    )
    (net (code "104") (name "Net-(LED24-PadGREEN_P)") (class "Default")
      (node (ref "LED24") (pin "GREEN_P") (pinfunction "GREEN_P_GREEN_P") (pintype "input"))
      (node (ref "R6") (pin "1") (pinfunction "1_1") (pintype "passive"))
    )
    (net (code "105") (name "Net-(LED24-PadRED_P)") (class "Default")
      (node (ref "LED24") (pin "RED_P") (pinfunction "RED_P_RED_P") (pintype "input"))
      (node (ref "R5") (pin "1") (pinfunction "1_1") (pintype "passive"))
    )
    (net (code "106") (name "Net-(LED24-PadWHITE_P)") (class "Default")
      (node (ref "LED24") (pin "WHITE_P") (pinfunction "WHITE_P_WHITE_P") (pintype "input"))
      (node (ref "R8") (pin "1") (pinfunction "1_1") (pintype "passive"))
    )
    (net (code "107") (name "RED") (class "Default")
      (node (ref "F4") (pin "2") (pinfunction "2_2") (pintype "passive"))
      (node (ref "J2") (pin "5") (pinfunction "5_5") (pintype "passive"))
      (node (ref "JP8") (pin "2") (pinfunction "2_2") (pintype "passive"))
      (node (ref "R5") (pin "2") (pinfunction "2_2") (pintype "passive"))
    )
    (net (code "108") (name "RED_BRG") (class "Default")
      (node (ref "JP6") (pin "1") (pinfunction "1_1") (pintype "passive"))
      (node (ref "R1") (pin "2") (pinfunction "2_2") (pintype "passive"))
    )
    (net (code "109") (name "RED_IN") (class "Default")
      (node (ref "D4") (pin "K") (pinfunction "K_K") (pintype "passive"))
      (node (ref "F4") (pin "1") (pinfunction "1_1") (pintype "passive"))
      (node (ref "J1") (pin "1") (pinfunction "1_1") (pintype "passive"))
    )
    (net (code "110") (name "WHITE") (class "Default")
      (node (ref "F2") (pin "2") (pinfunction "2_2") (pintype "passive"))
      (node (ref "J2") (pin "3") (pinfunction "3_3") (pintype "passive"))
      (node (ref "JP3") (pin "2") (pinfunction "2_2") (pintype "passive"))
      (node (ref "R8") (pin "2") (pinfunction "2_2") (pintype "passive"))
    )
    (net (code "111") (name "WHITE_BRG") (class "Default")
      (node (ref "JP3") (pin "1") (pinfunction "1_1") (pintype "passive"))
      (node (ref "R4") (pin "2") (pinfunction "2_2") (pintype "passive"))
    )
    (net (code "112") (name "WHITE_IN") (class "Default")
      (node (ref "D2") (pin "K") (pinfunction "K_K") (pintype "passive"))
      (node (ref "F2") (pin "1") (pinfunction "1_1") (pintype "passive"))
      (node (ref "J1") (pin "3") (pinfunction "3_3") (pintype "passive"))
    )
  )
)
